# 1.net
KiCad netlist of a schematic drawn in Altium Designer
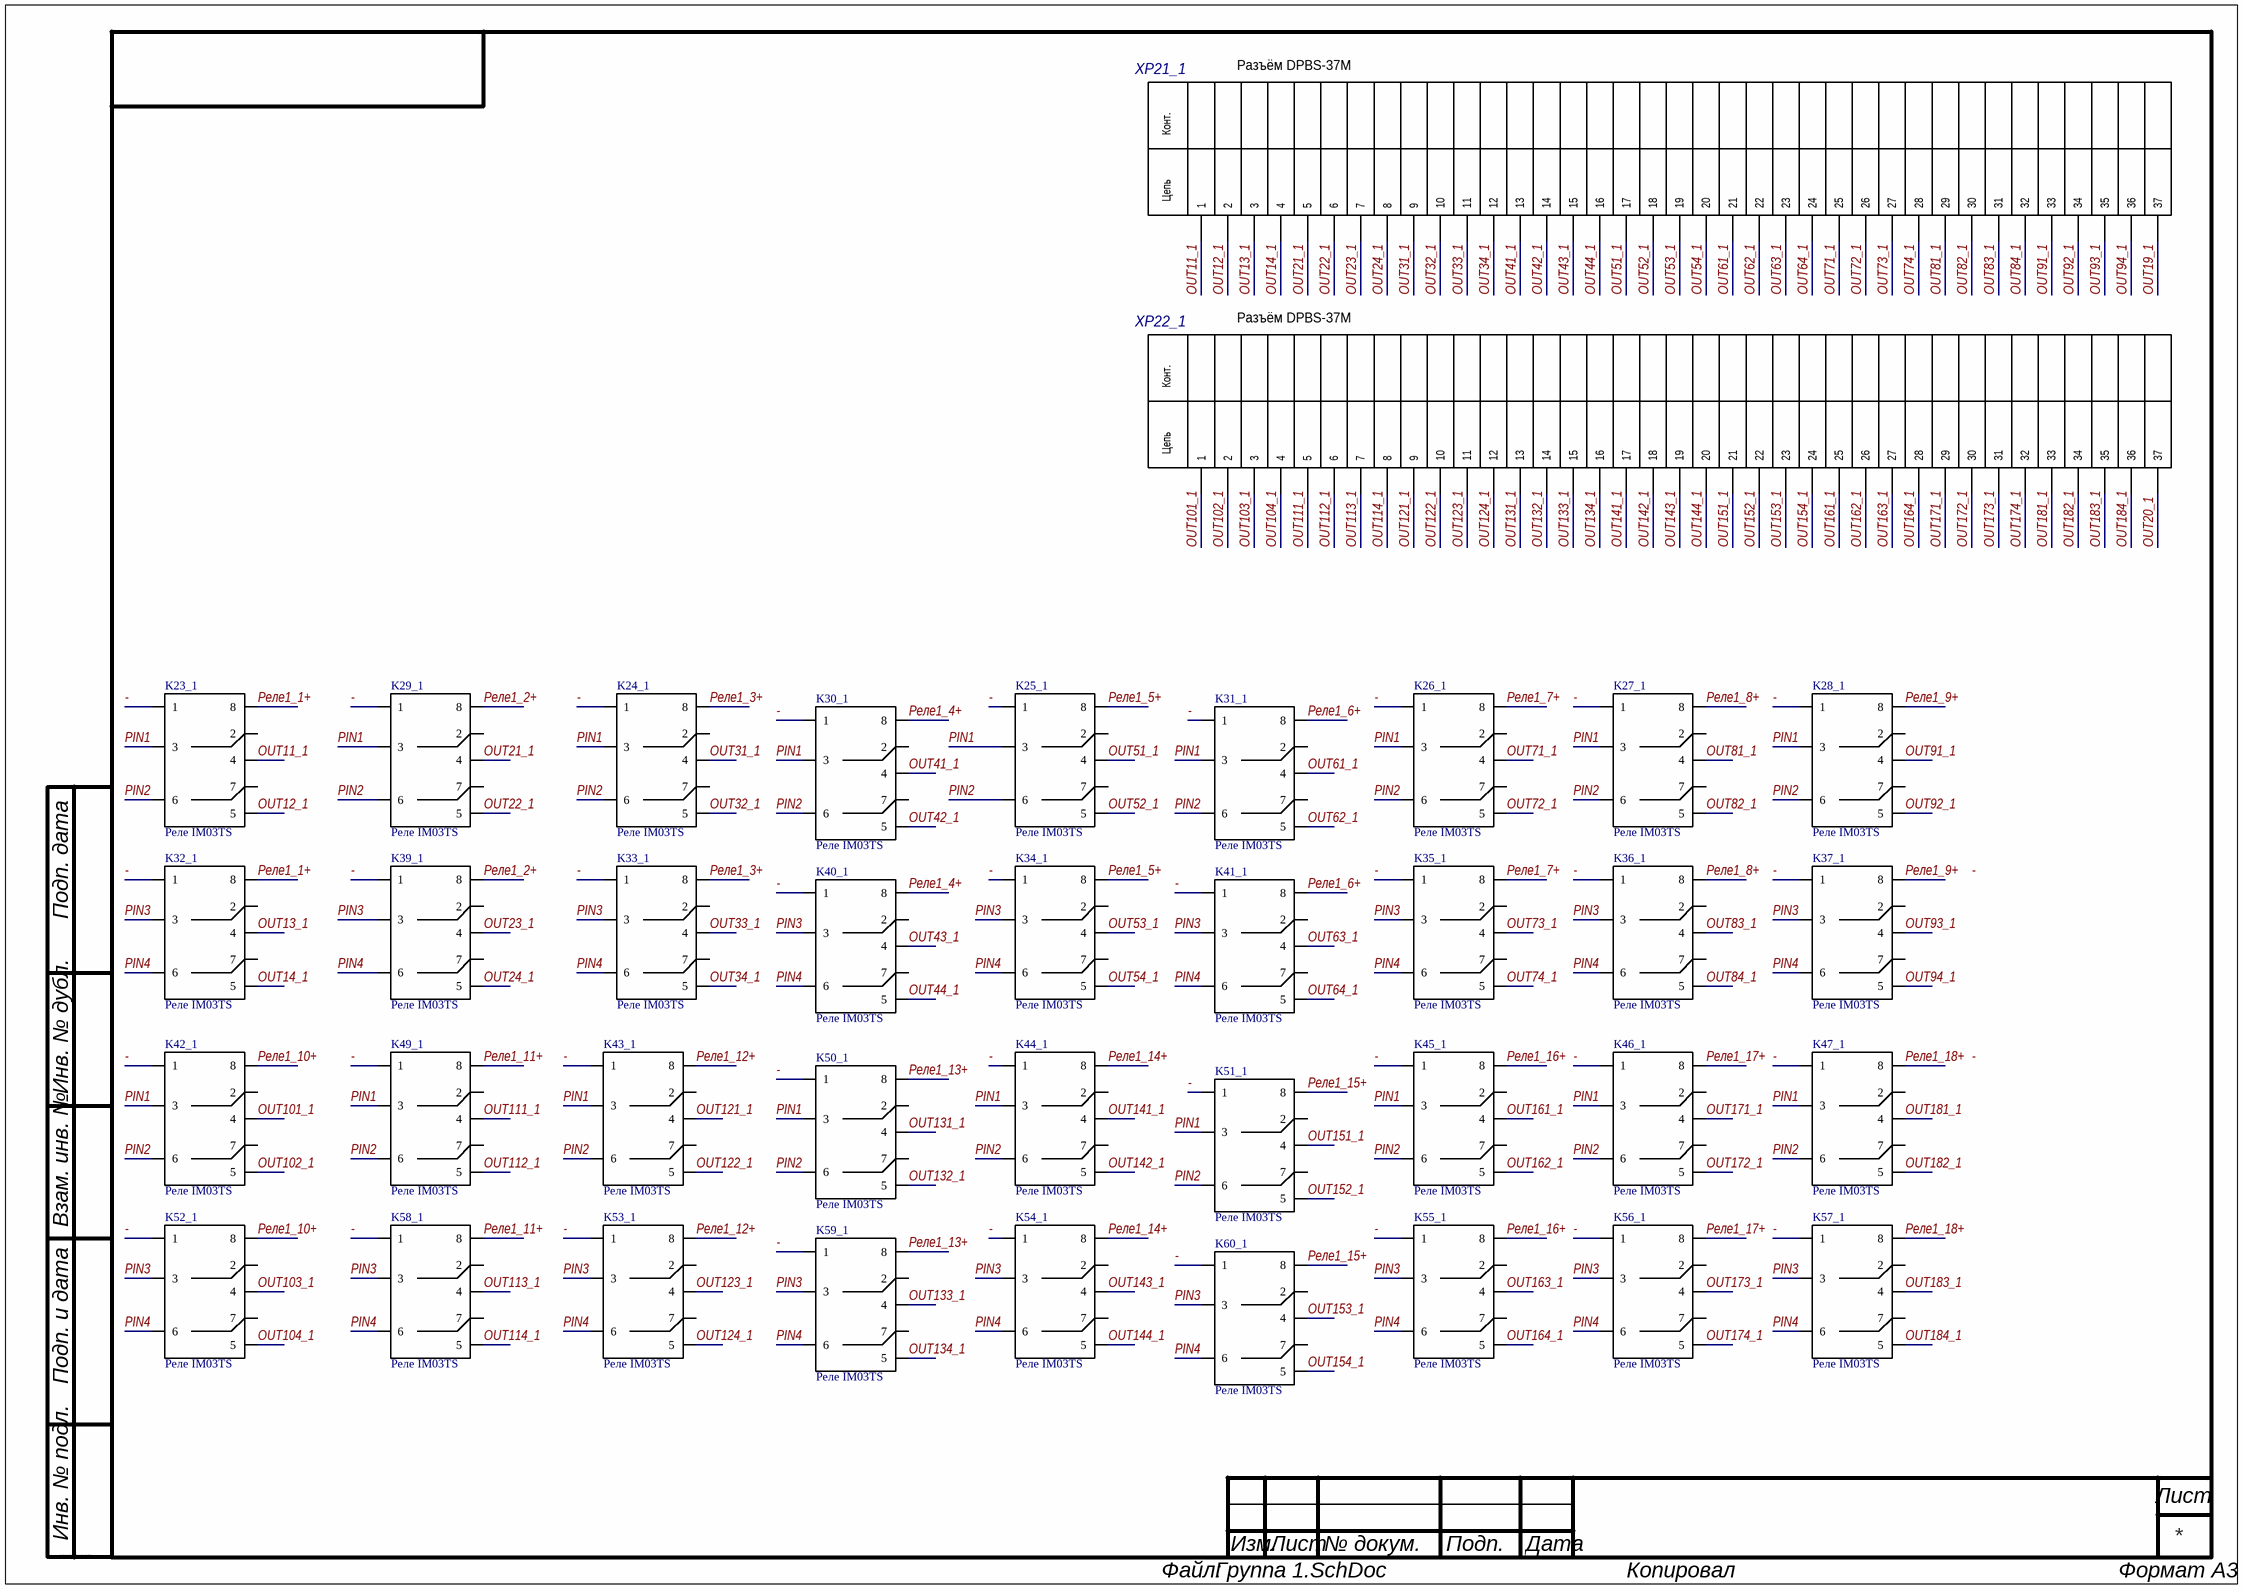
[diagram p0: Группа 1.SchDoc]

(export (version "E")
  (design (tool "Eeschema 10.0.6"))
  (components
    (comp (ref "K23_1")
      (value "Реле IM03TS")
      (footprint "IM03TS")
      (description "Реле")
      (libsource (lib "MainLibrary") (part "IM03TS"))
    )
    (comp (ref "K24_1")
      (value "Реле IM03TS")
      (footprint "IM03TS")
      (description "Реле")
      (libsource (lib "MainLibrary") (part "IM03TS"))
    )
    (comp (ref "K25_1")
      (value "Реле IM03TS")
      (footprint "IM03TS")
      (description "Реле")
      (libsource (lib "MainLibrary") (part "IM03TS"))
    )
    (comp (ref "K26_1")
      (value "Реле IM03TS")
      (footprint "IM03TS")
      (description "Реле")
      (libsource (lib "MainLibrary") (part "IM03TS"))
    )
    (comp (ref "K27_1")
      (value "Реле IM03TS")
      (footprint "IM03TS")
      (description "Реле")
      (libsource (lib "MainLibrary") (part "IM03TS"))
    )
    (comp (ref "K28_1")
      (value "Реле IM03TS")
      (footprint "IM03TS")
      (description "Реле")
      (libsource (lib "MainLibrary") (part "IM03TS"))
    )
    (comp (ref "K29_1")
      (value "Реле IM03TS")
      (footprint "IM03TS")
      (description "Реле")
      (libsource (lib "MainLibrary") (part "IM03TS"))
    )
    (comp (ref "K30_1")
      (value "Реле IM03TS")
      (footprint "IM03TS")
      (description "Реле")
      (libsource (lib "MainLibrary") (part "IM03TS"))
    )
    (comp (ref "K31_1")
      (value "Реле IM03TS")
      (footprint "IM03TS")
      (description "Реле")
      (libsource (lib "MainLibrary") (part "IM03TS"))
    )
    (comp (ref "K32_1")
      (value "Реле IM03TS")
      (footprint "IM03TS")
      (description "Реле")
      (libsource (lib "MainLibrary") (part "IM03TS"))
    )
    (comp (ref "K33_1")
      (value "Реле IM03TS")
      (footprint "IM03TS")
      (description "Реле")
      (libsource (lib "MainLibrary") (part "IM03TS"))
    )
    (comp (ref "K34_1")
      (value "Реле IM03TS")
      (footprint "IM03TS")
      (description "Реле")
      (libsource (lib "MainLibrary") (part "IM03TS"))
    )
    (comp (ref "K35_1")
      (value "Реле IM03TS")
      (footprint "IM03TS")
      (description "Реле")
      (libsource (lib "MainLibrary") (part "IM03TS"))
    )
    (comp (ref "K36_1")
      (value "Реле IM03TS")
      (footprint "IM03TS")
      (description "Реле")
      (libsource (lib "MainLibrary") (part "IM03TS"))
    )
    (comp (ref "K37_1")
      (value "Реле IM03TS")
      (footprint "IM03TS")
      (description "Реле")
      (libsource (lib "MainLibrary") (part "IM03TS"))
    )
    (comp (ref "K39_1")
      (value "Реле IM03TS")
      (footprint "IM03TS")
      (description "Реле")
      (libsource (lib "MainLibrary") (part "IM03TS"))
    )
    (comp (ref "K40_1")
      (value "Реле IM03TS")
      (footprint "IM03TS")
      (description "Реле")
      (libsource (lib "MainLibrary") (part "IM03TS"))
    )
    (comp (ref "K41_1")
      (value "Реле IM03TS")
      (footprint "IM03TS")
      (description "Реле")
      (libsource (lib "MainLibrary") (part "IM03TS"))
    )
    (comp (ref "K42_1")
      (value "Реле IM03TS")
      (footprint "IM03TS")
      (description "Реле")
      (libsource (lib "MainLibrary") (part "IM03TS"))
    )
    (comp (ref "K43_1")
      (value "Реле IM03TS")
      (footprint "IM03TS")
      (description "Реле")
      (libsource (lib "MainLibrary") (part "IM03TS"))
    )
    (comp (ref "K44_1")
      (value "Реле IM03TS")
      (footprint "IM03TS")
      (description "Реле")
      (libsource (lib "MainLibrary") (part "IM03TS"))
    )
    (comp (ref "K45_1")
      (value "Реле IM03TS")
      (footprint "IM03TS")
      (description "Реле")
      (libsource (lib "MainLibrary") (part "IM03TS"))
    )
    (comp (ref "K46_1")
      (value "Реле IM03TS")
      (footprint "IM03TS")
      (description "Реле")
      (libsource (lib "MainLibrary") (part "IM03TS"))
    )
    (comp (ref "K47_1")
      (value "Реле IM03TS")
      (footprint "IM03TS")
      (description "Реле")
      (libsource (lib "MainLibrary") (part "IM03TS"))
    )
    (comp (ref "K49_1")
      (value "Реле IM03TS")
      (footprint "IM03TS")
      (description "Реле")
      (libsource (lib "MainLibrary") (part "IM03TS"))
    )
    (comp (ref "K50_1")
      (value "Реле IM03TS")
      (footprint "IM03TS")
      (description "Реле")
      (libsource (lib "MainLibrary") (part "IM03TS"))
    )
    (comp (ref "K51_1")
      (value "Реле IM03TS")
      (footprint "IM03TS")
      (description "Реле")
      (libsource (lib "MainLibrary") (part "IM03TS"))
    )
    (comp (ref "K52_1")
      (value "Реле IM03TS")
      (footprint "IM03TS")
      (description "Реле")
      (libsource (lib "MainLibrary") (part "IM03TS"))
    )
    (comp (ref "K53_1")
      (value "Реле IM03TS")
      (footprint "IM03TS")
      (description "Реле")
      (libsource (lib "MainLibrary") (part "IM03TS"))
    )
    (comp (ref "K54_1")
      (value "Реле IM03TS")
      (footprint "IM03TS")
      (description "Реле")
      (libsource (lib "MainLibrary") (part "IM03TS"))
    )
    (comp (ref "K55_1")
      (value "Реле IM03TS")
      (footprint "IM03TS")
      (description "Реле")
      (libsource (lib "MainLibrary") (part "IM03TS"))
    )
    (comp (ref "K56_1")
      (value "Реле IM03TS")
      (footprint "IM03TS")
      (description "Реле")
      (libsource (lib "MainLibrary") (part "IM03TS"))
    )
    (comp (ref "K57_1")
      (value "Реле IM03TS")
      (footprint "IM03TS")
      (description "Реле")
      (libsource (lib "MainLibrary") (part "IM03TS"))
    )
    (comp (ref "K58_1")
      (value "Реле IM03TS")
      (footprint "IM03TS")
      (description "Реле")
      (libsource (lib "MainLibrary") (part "IM03TS"))
    )
    (comp (ref "K59_1")
      (value "Реле IM03TS")
      (footprint "IM03TS")
      (description "Реле")
      (libsource (lib "MainLibrary") (part "IM03TS"))
    )
    (comp (ref "K60_1")
      (value "Реле IM03TS")
      (footprint "IM03TS")
      (description "Реле")
      (libsource (lib "MainLibrary") (part "IM03TS"))
    )
    (comp (ref "XP21_1")
      (value "Разъём DPBS-37M")
      (footprint "DPBS-37M")
      (libsource (lib "MainLibrary") (part "DPBS-37M"))
    )
    (comp (ref "XP22_1")
      (value "Разъём DPBS-37M")
      (footprint "DPBS-37M")
      (libsource (lib "MainLibrary") (part "DPBS-37M"))
    )
  )
  (nets
    (net (code "1") (name "/-") (class "Default")
      (node (ref "K23_1") (pin "1") (pinfunction "1_1") (pintype "passive"))
      (node (ref "K24_1") (pin "1") (pinfunction "1_1") (pintype "passive"))
      (node (ref "K25_1") (pin "1") (pinfunction "1_1") (pintype "passive"))
      (node (ref "K26_1") (pin "1") (pinfunction "1_1") (pintype "passive"))
      (node (ref "K27_1") (pin "1") (pinfunction "1_1") (pintype "passive"))
      (node (ref "K28_1") (pin "1") (pinfunction "1_1") (pintype "passive"))
      (node (ref "K29_1") (pin "1") (pinfunction "1_1") (pintype "passive"))
      (node (ref "K30_1") (pin "1") (pinfunction "1_1") (pintype "passive"))
      (node (ref "K31_1") (pin "1") (pinfunction "1_1") (pintype "passive"))
      (node (ref "K32_1") (pin "1") (pinfunction "1_1") (pintype "passive"))
      (node (ref "K33_1") (pin "1") (pinfunction "1_1") (pintype "passive"))
      (node (ref "K34_1") (pin "1") (pinfunction "1_1") (pintype "passive"))
      (node (ref "K35_1") (pin "1") (pinfunction "1_1") (pintype "passive"))
      (node (ref "K36_1") (pin "1") (pinfunction "1_1") (pintype "passive"))
      (node (ref "K37_1") (pin "1") (pinfunction "1_1") (pintype "passive"))
      (node (ref "K39_1") (pin "1") (pinfunction "1_1") (pintype "passive"))
      (node (ref "K40_1") (pin "1") (pinfunction "1_1") (pintype "passive"))
      (node (ref "K41_1") (pin "1") (pinfunction "1_1") (pintype "passive"))
      (node (ref "K42_1") (pin "1") (pinfunction "1_1") (pintype "passive"))
      (node (ref "K43_1") (pin "1") (pinfunction "1_1") (pintype "passive"))
      (node (ref "K44_1") (pin "1") (pinfunction "1_1") (pintype "passive"))
      (node (ref "K45_1") (pin "1") (pinfunction "1_1") (pintype "passive"))
      (node (ref "K46_1") (pin "1") (pinfunction "1_1") (pintype "passive"))
      (node (ref "K47_1") (pin "1") (pinfunction "1_1") (pintype "passive"))
      (node (ref "K49_1") (pin "1") (pinfunction "1_1") (pintype "passive"))
      (node (ref "K50_1") (pin "1") (pinfunction "1_1") (pintype "passive"))
      (node (ref "K51_1") (pin "1") (pinfunction "1_1") (pintype "passive"))
      (node (ref "K52_1") (pin "1") (pinfunction "1_1") (pintype "passive"))
      (node (ref "K53_1") (pin "1") (pinfunction "1_1") (pintype "passive"))
      (node (ref "K54_1") (pin "1") (pinfunction "1_1") (pintype "passive"))
      (node (ref "K55_1") (pin "1") (pinfunction "1_1") (pintype "passive"))
      (node (ref "K56_1") (pin "1") (pinfunction "1_1") (pintype "passive"))
      (node (ref "K57_1") (pin "1") (pinfunction "1_1") (pintype "passive"))
      (node (ref "K58_1") (pin "1") (pinfunction "1_1") (pintype "passive"))
      (node (ref "K59_1") (pin "1") (pinfunction "1_1") (pintype "passive"))
      (node (ref "K60_1") (pin "1") (pinfunction "1_1") (pintype "passive"))
    )
    (net (code "2") (name "/OUT11_1") (class "Default")
      (node (ref "K23_1") (pin "4") (pinfunction "4_4") (pintype "passive"))
      (node (ref "XP21_1") (pin "1") (pinfunction "1_1") (pintype "passive"))
    )
    (net (code "3") (name "/OUT12_1") (class "Default")
      (node (ref "K23_1") (pin "5") (pinfunction "5_5") (pintype "passive"))
      (node (ref "XP21_1") (pin "2") (pinfunction "2_2") (pintype "passive"))
    )
    (net (code "4") (name "/OUT13_1") (class "Default")
      (node (ref "K32_1") (pin "4") (pinfunction "4_4") (pintype "passive"))
      (node (ref "XP21_1") (pin "3") (pinfunction "3_3") (pintype "passive"))
    )
    (net (code "5") (name "/OUT14_1") (class "Default")
      (node (ref "K32_1") (pin "5") (pinfunction "5_5") (pintype "passive"))
      (node (ref "XP21_1") (pin "4") (pinfunction "4_4") (pintype "passive"))
    )
    (net (code "6") (name "/OUT19_1") (class "Default")
      (node (ref "XP21_1") (pin "37") (pinfunction "37_37") (pintype "passive"))
    )
    (net (code "7") (name "/OUT20_1") (class "Default")
      (node (ref "XP22_1") (pin "37") (pinfunction "37_37") (pintype "passive"))
    )
    (net (code "8") (name "/OUT21_1") (class "Default")
      (node (ref "K29_1") (pin "4") (pinfunction "4_4") (pintype "passive"))
      (node (ref "XP21_1") (pin "5") (pinfunction "5_5") (pintype "passive"))
    )
    (net (code "9") (name "/OUT22_1") (class "Default")
      (node (ref "K29_1") (pin "5") (pinfunction "5_5") (pintype "passive"))
      (node (ref "XP21_1") (pin "6") (pinfunction "6_6") (pintype "passive"))
    )
    (net (code "10") (name "/OUT23_1") (class "Default")
      (node (ref "K39_1") (pin "4") (pinfunction "4_4") (pintype "passive"))
      (node (ref "XP21_1") (pin "7") (pinfunction "7_7") (pintype "passive"))
    )
    (net (code "11") (name "/OUT24_1") (class "Default")
      (node (ref "K39_1") (pin "5") (pinfunction "5_5") (pintype "passive"))
      (node (ref "XP21_1") (pin "8") (pinfunction "8_8") (pintype "passive"))
    )
    (net (code "12") (name "/OUT31_1") (class "Default")
      (node (ref "K24_1") (pin "4") (pinfunction "4_4") (pintype "passive"))
      (node (ref "XP21_1") (pin "9") (pinfunction "9_9") (pintype "passive"))
    )
    (net (code "13") (name "/OUT32_1") (class "Default")
      (node (ref "K24_1") (pin "5") (pinfunction "5_5") (pintype "passive"))
      (node (ref "XP21_1") (pin "10") (pinfunction "10_10") (pintype "passive"))
    )
    (net (code "14") (name "/OUT33_1") (class "Default")
      (node (ref "K33_1") (pin "4") (pinfunction "4_4") (pintype "passive"))
      (node (ref "XP21_1") (pin "11") (pinfunction "11_11") (pintype "passive"))
    )
    (net (code "15") (name "/OUT34_1") (class "Default")
      (node (ref "K33_1") (pin "5") (pinfunction "5_5") (pintype "passive"))
      (node (ref "XP21_1") (pin "12") (pinfunction "12_12") (pintype "passive"))
    )
    (net (code "16") (name "/OUT41_1") (class "Default")
      (node (ref "K30_1") (pin "4") (pinfunction "4_4") (pintype "passive"))
      (node (ref "XP21_1") (pin "13") (pinfunction "13_13") (pintype "passive"))
    )
    (net (code "17") (name "/OUT42_1") (class "Default")
      (node (ref "K30_1") (pin "5") (pinfunction "5_5") (pintype "passive"))
      (node (ref "XP21_1") (pin "14") (pinfunction "14_14") (pintype "passive"))
    )
    (net (code "18") (name "/OUT43_1") (class "Default")
      (node (ref "K40_1") (pin "4") (pinfunction "4_4") (pintype "passive"))
      (node (ref "XP21_1") (pin "15") (pinfunction "15_15") (pintype "passive"))
    )
    (net (code "19") (name "/OUT44_1") (class "Default")
      (node (ref "K40_1") (pin "5") (pinfunction "5_5") (pintype "passive"))
      (node (ref "XP21_1") (pin "16") (pinfunction "16_16") (pintype "passive"))
    )
    (net (code "20") (name "/OUT51_1") (class "Default")
      (node (ref "K25_1") (pin "4") (pinfunction "4_4") (pintype "passive"))
      (node (ref "XP21_1") (pin "17") (pinfunction "17_17") (pintype "passive"))
    )
    (net (code "21") (name "/OUT52_1") (class "Default")
      (node (ref "K25_1") (pin "5") (pinfunction "5_5") (pintype "passive"))
      (node (ref "XP21_1") (pin "18") (pinfunction "18_18") (pintype "passive"))
    )
    (net (code "22") (name "/OUT53_1") (class "Default")
      (node (ref "K34_1") (pin "4") (pinfunction "4_4") (pintype "passive"))
      (node (ref "XP21_1") (pin "19") (pinfunction "19_19") (pintype "passive"))
    )
    (net (code "23") (name "/OUT54_1") (class "Default")
      (node (ref "K34_1") (pin "5") (pinfunction "5_5") (pintype "passive"))
      (node (ref "XP21_1") (pin "20") (pinfunction "20_20") (pintype "passive"))
    )
    (net (code "24") (name "/OUT61_1") (class "Default")
      (node (ref "K31_1") (pin "4") (pinfunction "4_4") (pintype "passive"))
      (node (ref "XP21_1") (pin "21") (pinfunction "21_21") (pintype "passive"))
    )
    (net (code "25") (name "/OUT62_1") (class "Default")
      (node (ref "K31_1") (pin "5") (pinfunction "5_5") (pintype "passive"))
      (node (ref "XP21_1") (pin "22") (pinfunction "22_22") (pintype "passive"))
    )
    (net (code "26") (name "/OUT63_1") (class "Default")
      (node (ref "K41_1") (pin "4") (pinfunction "4_4") (pintype "passive"))
      (node (ref "XP21_1") (pin "23") (pinfunction "23_23") (pintype "passive"))
    )
    (net (code "27") (name "/OUT64_1") (class "Default")
      (node (ref "K41_1") (pin "5") (pinfunction "5_5") (pintype "passive"))
      (node (ref "XP21_1") (pin "24") (pinfunction "24_24") (pintype "passive"))
    )
    (net (code "28") (name "/OUT71_1") (class "Default")
      (node (ref "K26_1") (pin "4") (pinfunction "4_4") (pintype "passive"))
      (node (ref "XP21_1") (pin "25") (pinfunction "25_25") (pintype "passive"))
    )
    (net (code "29") (name "/OUT72_1") (class "Default")
      (node (ref "K26_1") (pin "5") (pinfunction "5_5") (pintype "passive"))
      (node (ref "XP21_1") (pin "26") (pinfunction "26_26") (pintype "passive"))
    )
    (net (code "30") (name "/OUT73_1") (class "Default")
      (node (ref "K35_1") (pin "4") (pinfunction "4_4") (pintype "passive"))
      (node (ref "XP21_1") (pin "27") (pinfunction "27_27") (pintype "passive"))
    )
    (net (code "31") (name "/OUT74_1") (class "Default")
      (node (ref "K35_1") (pin "5") (pinfunction "5_5") (pintype "passive"))
      (node (ref "XP21_1") (pin "28") (pinfunction "28_28") (pintype "passive"))
    )
    (net (code "32") (name "/OUT81_1") (class "Default")
      (node (ref "K27_1") (pin "4") (pinfunction "4_4") (pintype "passive"))
      (node (ref "XP21_1") (pin "29") (pinfunction "29_29") (pintype "passive"))
    )
    (net (code "33") (name "/OUT82_1") (class "Default")
      (node (ref "K27_1") (pin "5") (pinfunction "5_5") (pintype "passive"))
      (node (ref "XP21_1") (pin "30") (pinfunction "30_30") (pintype "passive"))
    )
    (net (code "34") (name "/OUT83_1") (class "Default")
      (node (ref "K36_1") (pin "4") (pinfunction "4_4") (pintype "passive"))
      (node (ref "XP21_1") (pin "31") (pinfunction "31_31") (pintype "passive"))
    )
    (net (code "35") (name "/OUT84_1") (class "Default")
      (node (ref "K36_1") (pin "5") (pinfunction "5_5") (pintype "passive"))
      (node (ref "XP21_1") (pin "32") (pinfunction "32_32") (pintype "passive"))
    )
    (net (code "36") (name "/OUT91_1") (class "Default")
      (node (ref "K28_1") (pin "4") (pinfunction "4_4") (pintype "passive"))
      (node (ref "XP21_1") (pin "33") (pinfunction "33_33") (pintype "passive"))
    )
    (net (code "37") (name "/OUT92_1") (class "Default")
      (node (ref "K28_1") (pin "5") (pinfunction "5_5") (pintype "passive"))
      (node (ref "XP21_1") (pin "34") (pinfunction "34_34") (pintype "passive"))
    )
    (net (code "38") (name "/OUT93_1") (class "Default")
      (node (ref "K37_1") (pin "4") (pinfunction "4_4") (pintype "passive"))
      (node (ref "XP21_1") (pin "35") (pinfunction "35_35") (pintype "passive"))
    )
    (net (code "39") (name "/OUT94_1") (class "Default")
      (node (ref "K37_1") (pin "5") (pinfunction "5_5") (pintype "passive"))
      (node (ref "XP21_1") (pin "36") (pinfunction "36_36") (pintype "passive"))
    )
    (net (code "40") (name "/OUT101_1") (class "Default")
      (node (ref "K42_1") (pin "4") (pinfunction "4_4") (pintype "passive"))
      (node (ref "XP22_1") (pin "1") (pinfunction "1_1") (pintype "passive"))
    )
    (net (code "41") (name "/OUT102_1") (class "Default")
      (node (ref "K42_1") (pin "5") (pinfunction "5_5") (pintype "passive"))
      (node (ref "XP22_1") (pin "2") (pinfunction "2_2") (pintype "passive"))
    )
    (net (code "42") (name "/OUT103_1") (class "Default")
      (node (ref "K52_1") (pin "4") (pinfunction "4_4") (pintype "passive"))
      (node (ref "XP22_1") (pin "3") (pinfunction "3_3") (pintype "passive"))
    )
    (net (code "43") (name "/OUT104_1") (class "Default")
      (node (ref "K52_1") (pin "5") (pinfunction "5_5") (pintype "passive"))
      (node (ref "XP22_1") (pin "4") (pinfunction "4_4") (pintype "passive"))
    )
    (net (code "44") (name "/OUT111_1") (class "Default")
      (node (ref "K49_1") (pin "4") (pinfunction "4_4") (pintype "passive"))
      (node (ref "XP22_1") (pin "5") (pinfunction "5_5") (pintype "passive"))
    )
    (net (code "45") (name "/OUT112_1") (class "Default")
      (node (ref "K49_1") (pin "5") (pinfunction "5_5") (pintype "passive"))
      (node (ref "XP22_1") (pin "6") (pinfunction "6_6") (pintype "passive"))
    )
    (net (code "46") (name "/OUT113_1") (class "Default")
      (node (ref "K58_1") (pin "4") (pinfunction "4_4") (pintype "passive"))
      (node (ref "XP22_1") (pin "7") (pinfunction "7_7") (pintype "passive"))
    )
    (net (code "47") (name "/OUT114_1") (class "Default")
      (node (ref "K58_1") (pin "5") (pinfunction "5_5") (pintype "passive"))
      (node (ref "XP22_1") (pin "8") (pinfunction "8_8") (pintype "passive"))
    )
    (net (code "48") (name "/OUT121_1") (class "Default")
      (node (ref "K43_1") (pin "4") (pinfunction "4_4") (pintype "passive"))
      (node (ref "XP22_1") (pin "9") (pinfunction "9_9") (pintype "passive"))
    )
    (net (code "49") (name "/OUT122_1") (class "Default")
      (node (ref "K43_1") (pin "5") (pinfunction "5_5") (pintype "passive"))
      (node (ref "XP22_1") (pin "10") (pinfunction "10_10") (pintype "passive"))
    )
    (net (code "50") (name "/OUT123_1") (class "Default")
      (node (ref "K53_1") (pin "4") (pinfunction "4_4") (pintype "passive"))
      (node (ref "XP22_1") (pin "11") (pinfunction "11_11") (pintype "passive"))
    )
    (net (code "51") (name "/OUT124_1") (class "Default")
      (node (ref "K53_1") (pin "5") (pinfunction "5_5") (pintype "passive"))
      (node (ref "XP22_1") (pin "12") (pinfunction "12_12") (pintype "passive"))
    )
    (net (code "52") (name "/OUT131_1") (class "Default")
      (node (ref "K50_1") (pin "4") (pinfunction "4_4") (pintype "passive"))
      (node (ref "XP22_1") (pin "13") (pinfunction "13_13") (pintype "passive"))
    )
    (net (code "53") (name "/OUT132_1") (class "Default")
      (node (ref "K50_1") (pin "5") (pinfunction "5_5") (pintype "passive"))
      (node (ref "XP22_1") (pin "14") (pinfunction "14_14") (pintype "passive"))
    )
    (net (code "54") (name "/OUT133_1") (class "Default")
      (node (ref "K59_1") (pin "4") (pinfunction "4_4") (pintype "passive"))
      (node (ref "XP22_1") (pin "15") (pinfunction "15_15") (pintype "passive"))
    )
    (net (code "55") (name "/OUT134_1") (class "Default")
      (node (ref "K59_1") (pin "5") (pinfunction "5_5") (pintype "passive"))
      (node (ref "XP22_1") (pin "16") (pinfunction "16_16") (pintype "passive"))
    )
    (net (code "56") (name "/OUT141_1") (class "Default")
      (node (ref "K44_1") (pin "4") (pinfunction "4_4") (pintype "passive"))
      (node (ref "XP22_1") (pin "17") (pinfunction "17_17") (pintype "passive"))
    )
    (net (code "57") (name "/OUT142_1") (class "Default")
      (node (ref "K44_1") (pin "5") (pinfunction "5_5") (pintype "passive"))
      (node (ref "XP22_1") (pin "18") (pinfunction "18_18") (pintype "passive"))
    )
    (net (code "58") (name "/OUT143_1") (class "Default")
      (node (ref "K54_1") (pin "4") (pinfunction "4_4") (pintype "passive"))
      (node (ref "XP22_1") (pin "19") (pinfunction "19_19") (pintype "passive"))
    )
    (net (code "59") (name "/OUT144_1") (class "Default")
      (node (ref "K54_1") (pin "5") (pinfunction "5_5") (pintype "passive"))
      (node (ref "XP22_1") (pin "20") (pinfunction "20_20") (pintype "passive"))
    )
    (net (code "60") (name "/OUT151_1") (class "Default")
      (node (ref "K51_1") (pin "4") (pinfunction "4_4") (pintype "passive"))
      (node (ref "XP22_1") (pin "21") (pinfunction "21_21") (pintype "passive"))
    )
    (net (code "61") (name "/OUT152_1") (class "Default")
      (node (ref "K51_1") (pin "5") (pinfunction "5_5") (pintype "passive"))
      (node (ref "XP22_1") (pin "22") (pinfunction "22_22") (pintype "passive"))
    )
    (net (code "62") (name "/OUT153_1") (class "Default")
      (node (ref "K60_1") (pin "4") (pinfunction "4_4") (pintype "passive"))
      (node (ref "XP22_1") (pin "23") (pinfunction "23_23") (pintype "passive"))
    )
    (net (code "63") (name "/OUT154_1") (class "Default")
      (node (ref "K60_1") (pin "5") (pinfunction "5_5") (pintype "passive"))
      (node (ref "XP22_1") (pin "24") (pinfunction "24_24") (pintype "passive"))
    )
    (net (code "64") (name "/OUT161_1") (class "Default")
      (node (ref "K45_1") (pin "4") (pinfunction "4_4") (pintype "passive"))
      (node (ref "XP22_1") (pin "25") (pinfunction "25_25") (pintype "passive"))
    )
    (net (code "65") (name "/OUT162_1") (class "Default")
      (node (ref "K45_1") (pin "5") (pinfunction "5_5") (pintype "passive"))
      (node (ref "XP22_1") (pin "26") (pinfunction "26_26") (pintype "passive"))
    )
    (net (code "66") (name "/OUT163_1") (class "Default")
      (node (ref "K55_1") (pin "4") (pinfunction "4_4") (pintype "passive"))
      (node (ref "XP22_1") (pin "27") (pinfunction "27_27") (pintype "passive"))
    )
    (net (code "67") (name "/OUT164_1") (class "Default")
      (node (ref "K55_1") (pin "5") (pinfunction "5_5") (pintype "passive"))
      (node (ref "XP22_1") (pin "28") (pinfunction "28_28") (pintype "passive"))
    )
    (net (code "68") (name "/OUT171_1") (class "Default")
      (node (ref "K46_1") (pin "4") (pinfunction "4_4") (pintype "passive"))
      (node (ref "XP22_1") (pin "29") (pinfunction "29_29") (pintype "passive"))
    )
    (net (code "69") (name "/OUT172_1") (class "Default")
      (node (ref "K46_1") (pin "5") (pinfunction "5_5") (pintype "passive"))
      (node (ref "XP22_1") (pin "30") (pinfunction "30_30") (pintype "passive"))
    )
    (net (code "70") (name "/OUT173_1") (class "Default")
      (node (ref "K56_1") (pin "4") (pinfunction "4_4") (pintype "passive"))
      (node (ref "XP22_1") (pin "31") (pinfunction "31_31") (pintype "passive"))
    )
    (net (code "71") (name "/OUT174_1") (class "Default")
      (node (ref "K56_1") (pin "5") (pinfunction "5_5") (pintype "passive"))
      (node (ref "XP22_1") (pin "32") (pinfunction "32_32") (pintype "passive"))
    )
    (net (code "72") (name "/OUT181_1") (class "Default")
      (node (ref "K47_1") (pin "4") (pinfunction "4_4") (pintype "passive"))
      (node (ref "XP22_1") (pin "33") (pinfunction "33_33") (pintype "passive"))
    )
    (net (code "73") (name "/OUT182_1") (class "Default")
      (node (ref "K47_1") (pin "5") (pinfunction "5_5") (pintype "passive"))
      (node (ref "XP22_1") (pin "34") (pinfunction "34_34") (pintype "passive"))
    )
    (net (code "74") (name "/OUT183_1") (class "Default")
      (node (ref "K57_1") (pin "4") (pinfunction "4_4") (pintype "passive"))
      (node (ref "XP22_1") (pin "35") (pinfunction "35_35") (pintype "passive"))
    )
    (net (code "75") (name "/OUT184_1") (class "Default")
      (node (ref "K57_1") (pin "5") (pinfunction "5_5") (pintype "passive"))
      (node (ref "XP22_1") (pin "36") (pinfunction "36_36") (pintype "passive"))
    )
    (net (code "76") (name "/PIN1") (class "Default")
      (node (ref "K23_1") (pin "3") (pinfunction "3_3") (pintype "passive"))
      (node (ref "K24_1") (pin "3") (pinfunction "3_3") (pintype "passive"))
      (node (ref "K25_1") (pin "3") (pinfunction "3_3") (pintype "passive"))
      (node (ref "K26_1") (pin "3") (pinfunction "3_3") (pintype "passive"))
      (node (ref "K27_1") (pin "3") (pinfunction "3_3") (pintype "passive"))
      (node (ref "K28_1") (pin "3") (pinfunction "3_3") (pintype "passive"))
      (node (ref "K29_1") (pin "3") (pinfunction "3_3") (pintype "passive"))
      (node (ref "K30_1") (pin "3") (pinfunction "3_3") (pintype "passive"))
      (node (ref "K31_1") (pin "3") (pinfunction "3_3") (pintype "passive"))
      (node (ref "K42_1") (pin "3") (pinfunction "3_3") (pintype "passive"))
      (node (ref "K43_1") (pin "3") (pinfunction "3_3") (pintype "passive"))
      (node (ref "K44_1") (pin "3") (pinfunction "3_3") (pintype "passive"))
      (node (ref "K45_1") (pin "3") (pinfunction "3_3") (pintype "passive"))
      (node (ref "K46_1") (pin "3") (pinfunction "3_3") (pintype "passive"))
      (node (ref "K47_1") (pin "3") (pinfunction "3_3") (pintype "passive"))
      (node (ref "K49_1") (pin "3") (pinfunction "3_3") (pintype "passive"))
      (node (ref "K50_1") (pin "3") (pinfunction "3_3") (pintype "passive"))
      (node (ref "K51_1") (pin "3") (pinfunction "3_3") (pintype "passive"))
    )
    (net (code "77") (name "/PIN2") (class "Default")
      (node (ref "K23_1") (pin "6") (pinfunction "6_6") (pintype "passive"))
      (node (ref "K24_1") (pin "6") (pinfunction "6_6") (pintype "passive"))
      (node (ref "K25_1") (pin "6") (pinfunction "6_6") (pintype "passive"))
      (node (ref "K26_1") (pin "6") (pinfunction "6_6") (pintype "passive"))
      (node (ref "K27_1") (pin "6") (pinfunction "6_6") (pintype "passive"))
      (node (ref "K28_1") (pin "6") (pinfunction "6_6") (pintype "passive"))
      (node (ref "K29_1") (pin "6") (pinfunction "6_6") (pintype "passive"))
      (node (ref "K30_1") (pin "6") (pinfunction "6_6") (pintype "passive"))
      (node (ref "K31_1") (pin "6") (pinfunction "6_6") (pintype "passive"))
      (node (ref "K42_1") (pin "6") (pinfunction "6_6") (pintype "passive"))
      (node (ref "K43_1") (pin "6") (pinfunction "6_6") (pintype "passive"))
      (node (ref "K44_1") (pin "6") (pinfunction "6_6") (pintype "passive"))
      (node (ref "K45_1") (pin "6") (pinfunction "6_6") (pintype "passive"))
      (node (ref "K46_1") (pin "6") (pinfunction "6_6") (pintype "passive"))
      (node (ref "K47_1") (pin "6") (pinfunction "6_6") (pintype "passive"))
      (node (ref "K49_1") (pin "6") (pinfunction "6_6") (pintype "passive"))
      (node (ref "K50_1") (pin "6") (pinfunction "6_6") (pintype "passive"))
      (node (ref "K51_1") (pin "6") (pinfunction "6_6") (pintype "passive"))
    )
    (net (code "78") (name "/PIN3") (class "Default")
      (node (ref "K32_1") (pin "3") (pinfunction "3_3") (pintype "passive"))
      (node (ref "K33_1") (pin "3") (pinfunction "3_3") (pintype "passive"))
      (node (ref "K34_1") (pin "3") (pinfunction "3_3") (pintype "passive"))
      (node (ref "K35_1") (pin "3") (pinfunction "3_3") (pintype "passive"))
      (node (ref "K36_1") (pin "3") (pinfunction "3_3") (pintype "passive"))
      (node (ref "K37_1") (pin "3") (pinfunction "3_3") (pintype "passive"))
      (node (ref "K39_1") (pin "3") (pinfunction "3_3") (pintype "passive"))
      (node (ref "K40_1") (pin "3") (pinfunction "3_3") (pintype "passive"))
      (node (ref "K41_1") (pin "3") (pinfunction "3_3") (pintype "passive"))
      (node (ref "K52_1") (pin "3") (pinfunction "3_3") (pintype "passive"))
      (node (ref "K53_1") (pin "3") (pinfunction "3_3") (pintype "passive"))
      (node (ref "K54_1") (pin "3") (pinfunction "3_3") (pintype "passive"))
      (node (ref "K55_1") (pin "3") (pinfunction "3_3") (pintype "passive"))
      (node (ref "K56_1") (pin "3") (pinfunction "3_3") (pintype "passive"))
      (node (ref "K57_1") (pin "3") (pinfunction "3_3") (pintype "passive"))
      (node (ref "K58_1") (pin "3") (pinfunction "3_3") (pintype "passive"))
      (node (ref "K59_1") (pin "3") (pinfunction "3_3") (pintype "passive"))
      (node (ref "K60_1") (pin "3") (pinfunction "3_3") (pintype "passive"))
    )
    (net (code "79") (name "/PIN4") (class "Default")
      (node (ref "K32_1") (pin "6") (pinfunction "6_6") (pintype "passive"))
      (node (ref "K33_1") (pin "6") (pinfunction "6_6") (pintype "passive"))
      (node (ref "K34_1") (pin "6") (pinfunction "6_6") (pintype "passive"))
      (node (ref "K35_1") (pin "6") (pinfunction "6_6") (pintype "passive"))
      (node (ref "K36_1") (pin "6") (pinfunction "6_6") (pintype "passive"))
      (node (ref "K37_1") (pin "6") (pinfunction "6_6") (pintype "passive"))
      (node (ref "K39_1") (pin "6") (pinfunction "6_6") (pintype "passive"))
      (node (ref "K40_1") (pin "6") (pinfunction "6_6") (pintype "passive"))
      (node (ref "K41_1") (pin "6") (pinfunction "6_6") (pintype "passive"))
      (node (ref "K52_1") (pin "6") (pinfunction "6_6") (pintype "passive"))
      (node (ref "K53_1") (pin "6") (pinfunction "6_6") (pintype "passive"))
      (node (ref "K54_1") (pin "6") (pinfunction "6_6") (pintype "passive"))
      (node (ref "K55_1") (pin "6") (pinfunction "6_6") (pintype "passive"))
      (node (ref "K56_1") (pin "6") (pinfunction "6_6") (pintype "passive"))
      (node (ref "K57_1") (pin "6") (pinfunction "6_6") (pintype "passive"))
      (node (ref "K58_1") (pin "6") (pinfunction "6_6") (pintype "passive"))
      (node (ref "K59_1") (pin "6") (pinfunction "6_6") (pintype "passive"))
      (node (ref "K60_1") (pin "6") (pinfunction "6_6") (pintype "passive"))
    )
    (net (code "80") (name "/Реле1_1+") (class "Default")
      (node (ref "K23_1") (pin "8") (pinfunction "8_8") (pintype "passive"))
      (node (ref "K32_1") (pin "8") (pinfunction "8_8") (pintype "passive"))
    )
    (net (code "81") (name "/Реле1_2+") (class "Default")
      (node (ref "K29_1") (pin "8") (pinfunction "8_8") (pintype "passive"))
      (node (ref "K39_1") (pin "8") (pinfunction "8_8") (pintype "passive"))
    )
    (net (code "82") (name "/Реле1_3+") (class "Default")
      (node (ref "K24_1") (pin "8") (pinfunction "8_8") (pintype "passive"))
      (node (ref "K33_1") (pin "8") (pinfunction "8_8") (pintype "passive"))
    )
    (net (code "83") (name "/Реле1_4+") (class "Default")
      (node (ref "K30_1") (pin "8") (pinfunction "8_8") (pintype "passive"))
      (node (ref "K40_1") (pin "8") (pinfunction "8_8") (pintype "passive"))
    )
    (net (code "84") (name "/Реле1_5+") (class "Default")
      (node (ref "K25_1") (pin "8") (pinfunction "8_8") (pintype "passive"))
      (node (ref "K34_1") (pin "8") (pinfunction "8_8") (pintype "passive"))
    )
    (net (code "85") (name "/Реле1_6+") (class "Default")
      (node (ref "K31_1") (pin "8") (pinfunction "8_8") (pintype "passive"))
      (node (ref "K41_1") (pin "8") (pinfunction "8_8") (pintype "passive"))
    )
    (net (code "86") (name "/Реле1_7+") (class "Default")
      (node (ref "K26_1") (pin "8") (pinfunction "8_8") (pintype "passive"))
      (node (ref "K35_1") (pin "8") (pinfunction "8_8") (pintype "passive"))
    )
    (net (code "87") (name "/Реле1_8+") (class "Default")
      (node (ref "K27_1") (pin "8") (pinfunction "8_8") (pintype "passive"))
      (node (ref "K36_1") (pin "8") (pinfunction "8_8") (pintype "passive"))
    )
    (net (code "88") (name "/Реле1_9+") (class "Default")
      (node (ref "K28_1") (pin "8") (pinfunction "8_8") (pintype "passive"))
      (node (ref "K37_1") (pin "8") (pinfunction "8_8") (pintype "passive"))
    )
    (net (code "89") (name "/Реле1_10+") (class "Default")
      (node (ref "K42_1") (pin "8") (pinfunction "8_8") (pintype "passive"))
      (node (ref "K52_1") (pin "8") (pinfunction "8_8") (pintype "passive"))
    )
    (net (code "90") (name "/Реле1_11+") (class "Default")
      (node (ref "K49_1") (pin "8") (pinfunction "8_8") (pintype "passive"))
      (node (ref "K58_1") (pin "8") (pinfunction "8_8") (pintype "passive"))
    )
    (net (code "91") (name "/Реле1_12+") (class "Default")
      (node (ref "K43_1") (pin "8") (pinfunction "8_8") (pintype "passive"))
      (node (ref "K53_1") (pin "8") (pinfunction "8_8") (pintype "passive"))
    )
    (net (code "92") (name "/Реле1_13+") (class "Default")
      (node (ref "K50_1") (pin "8") (pinfunction "8_8") (pintype "passive"))
      (node (ref "K59_1") (pin "8") (pinfunction "8_8") (pintype "passive"))
    )
    (net (code "93") (name "/Реле1_14+") (class "Default")
      (node (ref "K44_1") (pin "8") (pinfunction "8_8") (pintype "passive"))
      (node (ref "K54_1") (pin "8") (pinfunction "8_8") (pintype "passive"))
    )
    (net (code "94") (name "/Реле1_15+") (class "Default")
      (node (ref "K51_1") (pin "8") (pinfunction "8_8") (pintype "passive"))
      (node (ref "K60_1") (pin "8") (pinfunction "8_8") (pintype "passive"))
    )
    (net (code "95") (name "/Реле1_16+") (class "Default")
      (node (ref "K45_1") (pin "8") (pinfunction "8_8") (pintype "passive"))
      (node (ref "K55_1") (pin "8") (pinfunction "8_8") (pintype "passive"))
    )
    (net (code "96") (name "/Реле1_17+") (class "Default")
      (node (ref "K46_1") (pin "8") (pinfunction "8_8") (pintype "passive"))
      (node (ref "K56_1") (pin "8") (pinfunction "8_8") (pintype "passive"))
    )
    (net (code "97") (name "/Реле1_18+") (class "Default")
      (node (ref "K47_1") (pin "8") (pinfunction "8_8") (pintype "passive"))
      (node (ref "K57_1") (pin "8") (pinfunction "8_8") (pintype "passive"))
    )
    (net (code "98") (name "unconnected-(K23_1-Pad2)") (class "Default")
      (node (ref "K23_1") (pin "2") (pinfunction "2_2") (pintype "passive"))
    )
    (net (code "99") (name "unconnected-(K23_1-Pad7)") (class "Default")
      (node (ref "K23_1") (pin "7") (pinfunction "7_7") (pintype "passive"))
    )
    (net (code "100") (name "unconnected-(K24_1-Pad2)") (class "Default")
      (node (ref "K24_1") (pin "2") (pinfunction "2_2") (pintype "passive"))
    )
    (net (code "101") (name "unconnected-(K24_1-Pad7)") (class "Default")
      (node (ref "K24_1") (pin "7") (pinfunction "7_7") (pintype "passive"))
    )
    (net (code "102") (name "unconnected-(K25_1-Pad2)") (class "Default")
      (node (ref "K25_1") (pin "2") (pinfunction "2_2") (pintype "passive"))
    )
    (net (code "103") (name "unconnected-(K25_1-Pad7)") (class "Default")
      (node (ref "K25_1") (pin "7") (pinfunction "7_7") (pintype "passive"))
    )
    (net (code "104") (name "unconnected-(K26_1-Pad2)") (class "Default")
      (node (ref "K26_1") (pin "2") (pinfunction "2_2") (pintype "passive"))
    )
    (net (code "105") (name "unconnected-(K26_1-Pad7)") (class "Default")
      (node (ref "K26_1") (pin "7") (pinfunction "7_7") (pintype "passive"))
    )
    (net (code "106") (name "unconnected-(K27_1-Pad2)") (class "Default")
      (node (ref "K27_1") (pin "2") (pinfunction "2_2") (pintype "passive"))
    )
    (net (code "107") (name "unconnected-(K27_1-Pad7)") (class "Default")
      (node (ref "K27_1") (pin "7") (pinfunction "7_7") (pintype "passive"))
    )
    (net (code "108") (name "unconnected-(K28_1-Pad2)") (class "Default")
      (node (ref "K28_1") (pin "2") (pinfunction "2_2") (pintype "passive"))
    )
    (net (code "109") (name "unconnected-(K28_1-Pad7)") (class "Default")
      (node (ref "K28_1") (pin "7") (pinfunction "7_7") (pintype "passive"))
    )
    (net (code "110") (name "unconnected-(K29_1-Pad2)") (class "Default")
      (node (ref "K29_1") (pin "2") (pinfunction "2_2") (pintype "passive"))
    )
    (net (code "111") (name "unconnected-(K29_1-Pad7)") (class "Default")
      (node (ref "K29_1") (pin "7") (pinfunction "7_7") (pintype "passive"))
    )
    (net (code "112") (name "unconnected-(K30_1-Pad2)") (class "Default")
      (node (ref "K30_1") (pin "2") (pinfunction "2_2") (pintype "passive"))
    )
    (net (code "113") (name "unconnected-(K30_1-Pad7)") (class "Default")
      (node (ref "K30_1") (pin "7") (pinfunction "7_7") (pintype "passive"))
    )
    (net (code "114") (name "unconnected-(K31_1-Pad2)") (class "Default")
      (node (ref "K31_1") (pin "2") (pinfunction "2_2") (pintype "passive"))
    )
    (net (code "115") (name "unconnected-(K31_1-Pad7)") (class "Default")
      (node (ref "K31_1") (pin "7") (pinfunction "7_7") (pintype "passive"))
    )
    (net (code "116") (name "unconnected-(K32_1-Pad2)") (class "Default")
      (node (ref "K32_1") (pin "2") (pinfunction "2_2") (pintype "passive"))
    )
    (net (code "117") (name "unconnected-(K32_1-Pad7)") (class "Default")
      (node (ref "K32_1") (pin "7") (pinfunction "7_7") (pintype "passive"))
    )
    (net (code "118") (name "unconnected-(K33_1-Pad2)") (class "Default")
      (node (ref "K33_1") (pin "2") (pinfunction "2_2") (pintype "passive"))
    )
    (net (code "119") (name "unconnected-(K33_1-Pad7)") (class "Default")
      (node (ref "K33_1") (pin "7") (pinfunction "7_7") (pintype "passive"))
    )
    (net (code "120") (name "unconnected-(K34_1-Pad2)") (class "Default")
      (node (ref "K34_1") (pin "2") (pinfunction "2_2") (pintype "passive"))
    )
    (net (code "121") (name "unconnected-(K34_1-Pad7)") (class "Default")
      (node (ref "K34_1") (pin "7") (pinfunction "7_7") (pintype "passive"))
    )
    (net (code "122") (name "unconnected-(K35_1-Pad2)") (class "Default")
      (node (ref "K35_1") (pin "2") (pinfunction "2_2") (pintype "passive"))
    )
    (net (code "123") (name "unconnected-(K35_1-Pad7)") (class "Default")
      (node (ref "K35_1") (pin "7") (pinfunction "7_7") (pintype "passive"))
    )
    (net (code "124") (name "unconnected-(K36_1-Pad2)") (class "Default")
      (node (ref "K36_1") (pin "2") (pinfunction "2_2") (pintype "passive"))
    )
    (net (code "125") (name "unconnected-(K36_1-Pad7)") (class "Default")
      (node (ref "K36_1") (pin "7") (pinfunction "7_7") (pintype "passive"))
    )
    (net (code "126") (name "unconnected-(K37_1-Pad2)") (class "Default")
      (node (ref "K37_1") (pin "2") (pinfunction "2_2") (pintype "passive"))
    )
    (net (code "127") (name "unconnected-(K37_1-Pad7)") (class "Default")
      (node (ref "K37_1") (pin "7") (pinfunction "7_7") (pintype "passive"))
    )
    (net (code "128") (name "unconnected-(K39_1-Pad2)") (class "Default")
      (node (ref "K39_1") (pin "2") (pinfunction "2_2") (pintype "passive"))
    )
    (net (code "129") (name "unconnected-(K39_1-Pad7)") (class "Default")
      (node (ref "K39_1") (pin "7") (pinfunction "7_7") (pintype "passive"))
    )
    (net (code "130") (name "unconnected-(K40_1-Pad2)") (class "Default")
      (node (ref "K40_1") (pin "2") (pinfunction "2_2") (pintype "passive"))
    )
    (net (code "131") (name "unconnected-(K40_1-Pad7)") (class "Default")
      (node (ref "K40_1") (pin "7") (pinfunction "7_7") (pintype "passive"))
    )
    (net (code "132") (name "unconnected-(K41_1-Pad2)") (class "Default")
      (node (ref "K41_1") (pin "2") (pinfunction "2_2") (pintype "passive"))
    )
    (net (code "133") (name "unconnected-(K41_1-Pad7)") (class "Default")
      (node (ref "K41_1") (pin "7") (pinfunction "7_7") (pintype "passive"))
    )
    (net (code "134") (name "unconnected-(K42_1-Pad2)") (class "Default")
      (node (ref "K42_1") (pin "2") (pinfunction "2_2") (pintype "passive"))
    )
    (net (code "135") (name "unconnected-(K42_1-Pad7)") (class "Default")
      (node (ref "K42_1") (pin "7") (pinfunction "7_7") (pintype "passive"))
    )
    (net (code "136") (name "unconnected-(K43_1-Pad2)") (class "Default")
      (node (ref "K43_1") (pin "2") (pinfunction "2_2") (pintype "passive"))
    )
    (net (code "137") (name "unconnected-(K43_1-Pad7)") (class "Default")
      (node (ref "K43_1") (pin "7") (pinfunction "7_7") (pintype "passive"))
    )
    (net (code "138") (name "unconnected-(K44_1-Pad2)") (class "Default")
      (node (ref "K44_1") (pin "2") (pinfunction "2_2") (pintype "passive"))
    )
    (net (code "139") (name "unconnected-(K44_1-Pad7)") (class "Default")
      (node (ref "K44_1") (pin "7") (pinfunction "7_7") (pintype "passive"))
    )
    (net (code "140") (name "unconnected-(K45_1-Pad2)") (class "Default")
      (node (ref "K45_1") (pin "2") (pinfunction "2_2") (pintype "passive"))
    )
    (net (code "141") (name "unconnected-(K45_1-Pad7)") (class "Default")
      (node (ref "K45_1") (pin "7") (pinfunction "7_7") (pintype "passive"))
    )
    (net (code "142") (name "unconnected-(K46_1-Pad2)") (class "Default")
      (node (ref "K46_1") (pin "2") (pinfunction "2_2") (pintype "passive"))
    )
    (net (code "143") (name "unconnected-(K46_1-Pad7)") (class "Default")
      (node (ref "K46_1") (pin "7") (pinfunction "7_7") (pintype "passive"))
    )
    (net (code "144") (name "unconnected-(K47_1-Pad2)") (class "Default")
      (node (ref "K47_1") (pin "2") (pinfunction "2_2") (pintype "passive"))
    )
    (net (code "145") (name "unconnected-(K47_1-Pad7)") (class "Default")
      (node (ref "K47_1") (pin "7") (pinfunction "7_7") (pintype "passive"))
    )
    (net (code "146") (name "unconnected-(K49_1-Pad2)") (class "Default")
      (node (ref "K49_1") (pin "2") (pinfunction "2_2") (pintype "passive"))
    )
    (net (code "147") (name "unconnected-(K49_1-Pad7)") (class "Default")
      (node (ref "K49_1") (pin "7") (pinfunction "7_7") (pintype "passive"))
    )
    (net (code "148") (name "unconnected-(K50_1-Pad2)") (class "Default")
      (node (ref "K50_1") (pin "2") (pinfunction "2_2") (pintype "passive"))
    )
    (net (code "149") (name "unconnected-(K50_1-Pad7)") (class "Default")
      (node (ref "K50_1") (pin "7") (pinfunction "7_7") (pintype "passive"))
    )
    (net (code "150") (name "unconnected-(K51_1-Pad2)") (class "Default")
      (node (ref "K51_1") (pin "2") (pinfunction "2_2") (pintype "passive"))
    )
    (net (code "151") (name "unconnected-(K51_1-Pad7)") (class "Default")
      (node (ref "K51_1") (pin "7") (pinfunction "7_7") (pintype "passive"))
    )
    (net (code "152") (name "unconnected-(K52_1-Pad2)") (class "Default")
      (node (ref "K52_1") (pin "2") (pinfunction "2_2") (pintype "passive"))
    )
    (net (code "153") (name "unconnected-(K52_1-Pad7)") (class "Default")
      (node (ref "K52_1") (pin "7") (pinfunction "7_7") (pintype "passive"))
    )
    (net (code "154") (name "unconnected-(K53_1-Pad2)") (class "Default")
      (node (ref "K53_1") (pin "2") (pinfunction "2_2") (pintype "passive"))
    )
    (net (code "155") (name "unconnected-(K53_1-Pad7)") (class "Default")
      (node (ref "K53_1") (pin "7") (pinfunction "7_7") (pintype "passive"))
    )
    (net (code "156") (name "unconnected-(K54_1-Pad2)") (class "Default")
      (node (ref "K54_1") (pin "2") (pinfunction "2_2") (pintype "passive"))
    )
    (net (code "157") (name "unconnected-(K54_1-Pad7)") (class "Default")
      (node (ref "K54_1") (pin "7") (pinfunction "7_7") (pintype "passive"))
    )
    (net (code "158") (name "unconnected-(K55_1-Pad2)") (class "Default")
      (node (ref "K55_1") (pin "2") (pinfunction "2_2") (pintype "passive"))
    )
    (net (code "159") (name "unconnected-(K55_1-Pad7)") (class "Default")
      (node (ref "K55_1") (pin "7") (pinfunction "7_7") (pintype "passive"))
    )
    (net (code "160") (name "unconnected-(K56_1-Pad2)") (class "Default")
      (node (ref "K56_1") (pin "2") (pinfunction "2_2") (pintype "passive"))
    )
    (net (code "161") (name "unconnected-(K56_1-Pad7)") (class "Default")
      (node (ref "K56_1") (pin "7") (pinfunction "7_7") (pintype "passive"))
    )
    (net (code "162") (name "unconnected-(K57_1-Pad2)") (class "Default")
      (node (ref "K57_1") (pin "2") (pinfunction "2_2") (pintype "passive"))
    )
    (net (code "163") (name "unconnected-(K57_1-Pad7)") (class "Default")
      (node (ref "K57_1") (pin "7") (pinfunction "7_7") (pintype "passive"))
    )
    (net (code "164") (name "unconnected-(K58_1-Pad2)") (class "Default")
      (node (ref "K58_1") (pin "2") (pinfunction "2_2") (pintype "passive"))
    )
    (net (code "165") (name "unconnected-(K58_1-Pad7)") (class "Default")
      (node (ref "K58_1") (pin "7") (pinfunction "7_7") (pintype "passive"))
    )
    (net (code "166") (name "unconnected-(K59_1-Pad2)") (class "Default")
      (node (ref "K59_1") (pin "2") (pinfunction "2_2") (pintype "passive"))
    )
    (net (code "167") (name "unconnected-(K59_1-Pad7)") (class "Default")
      (node (ref "K59_1") (pin "7") (pinfunction "7_7") (pintype "passive"))
    )
    (net (code "168") (name "unconnected-(K60_1-Pad2)") (class "Default")
      (node (ref "K60_1") (pin "2") (pinfunction "2_2") (pintype "passive"))
    )
    (net (code "169") (name "unconnected-(K60_1-Pad7)") (class "Default")
      (node (ref "K60_1") (pin "7") (pinfunction "7_7") (pintype "passive"))
    )
  )
)
